# Comu_485.net
KiCad netlist of a schematic drawn in Altium Designer
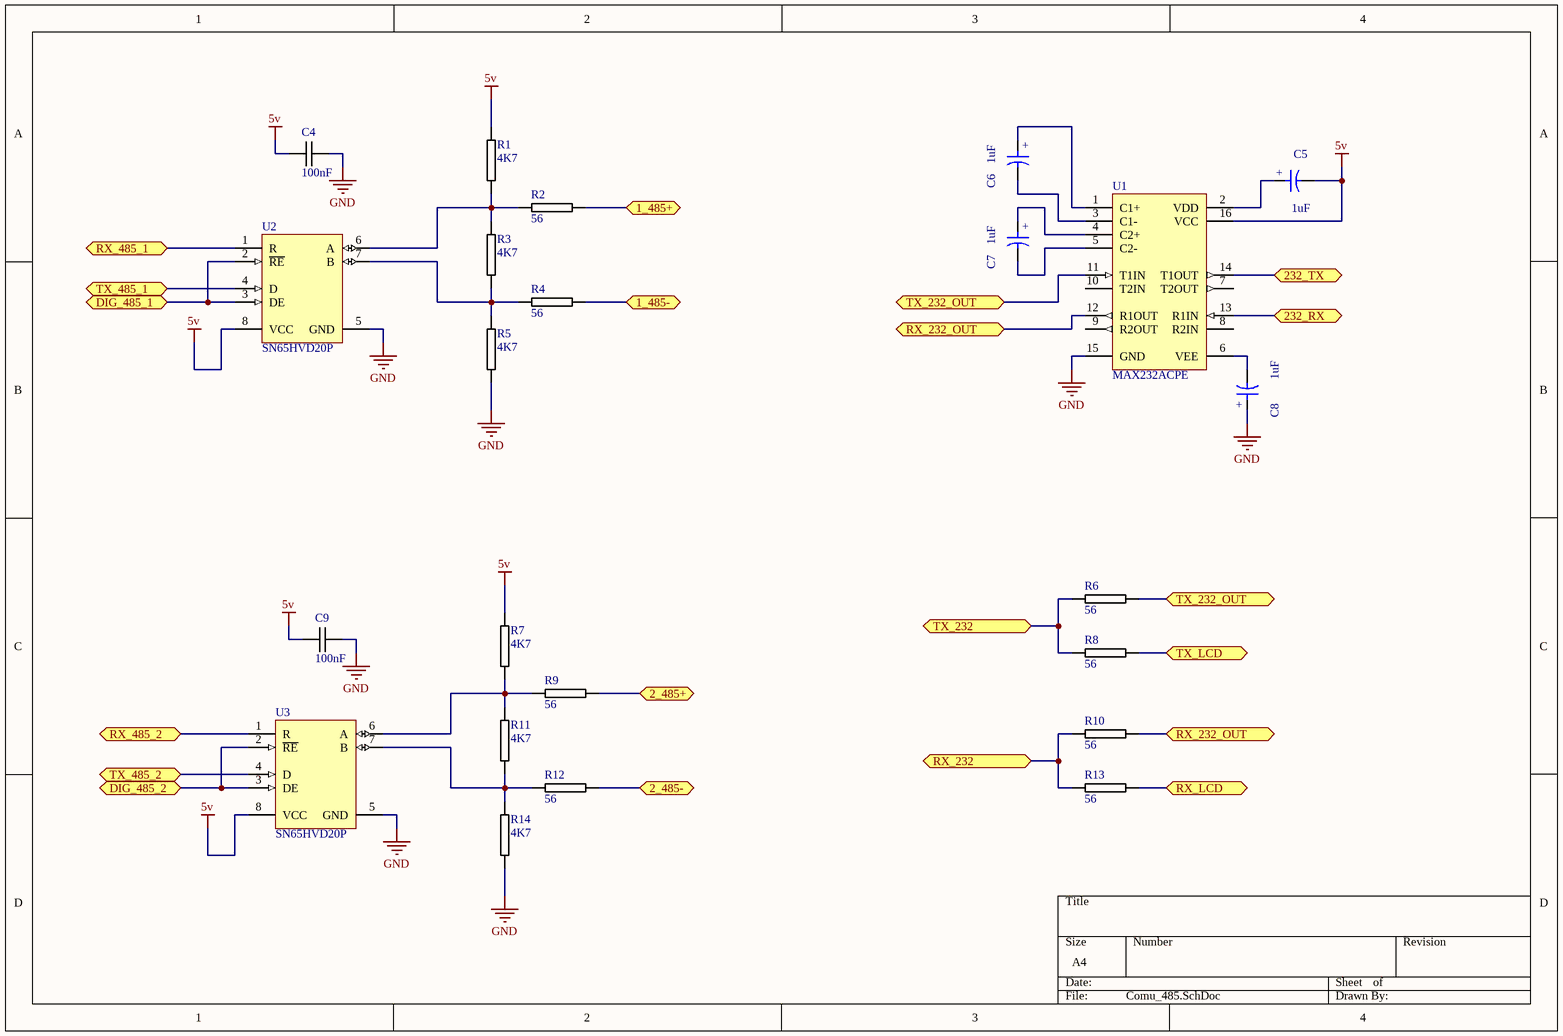
[diagram p0: Comu_485.SchDoc]

(export (version "E")
  (design (tool "Eeschema 10.0.6"))
  (components
    (comp (ref "C4")
      (value "100nF")
      (footprint "0805C-TBD")
      (description "CAPACITOR 0805 CERAMIC")
      (libsource (lib "vh_altium_library") (part "0805C-100nF-25V-X7R-MUR"))
    )
    (comp (ref "C5")
      (value "1uF")
      (footprint "CAPPRB254-450X710")
      (description "Polarised capacitor")
      (fields
        (field (name "PART NUMBER") "CTEB_1UF_35V_10%_254-450X710")
        (field (name "VOLTAGE") "35V")
        (field (name "AUTHOR") "CERN DEM JLC")
      )
      (libsource (lib "Capacitors") (part "Capacitor - polarized"))
    )
    (comp (ref "C6")
      (value "1uF")
      (footprint "CAPPRB254-450X710")
      (description "Polarised capacitor")
      (fields
        (field (name "PART NUMBER") "CTEB_1UF_35V_10%_254-450X710")
        (field (name "VOLTAGE") "35V")
        (field (name "AUTHOR") "CERN DEM JLC")
      )
      (libsource (lib "Capacitors") (part "Capacitor - polarized"))
    )
    (comp (ref "C7")
      (value "1uF")
      (footprint "CAPPRB254-450X710")
      (description "Polarised capacitor")
      (fields
        (field (name "PART NUMBER") "CTEB_1UF_35V_10%_254-450X710")
        (field (name "VOLTAGE") "35V")
        (field (name "AUTHOR") "CERN DEM JLC")
      )
      (libsource (lib "Capacitors") (part "Capacitor - polarized"))
    )
    (comp (ref "C8")
      (value "1uF")
      (footprint "CAPPRB254-450X710")
      (description "Polarised capacitor")
      (fields
        (field (name "PART NUMBER") "CTEB_1UF_35V_10%_254-450X710")
        (field (name "VOLTAGE") "35V")
        (field (name "AUTHOR") "CERN DEM JLC")
      )
      (libsource (lib "Capacitors") (part "Capacitor - polarized"))
    )
    (comp (ref "C9")
      (value "100nF")
      (footprint "0805C-TBD")
      (description "CAPACITOR 0805 CERAMIC")
      (libsource (lib "vh_altium_library") (part "0805C-100nF-25V-X7R-MUR"))
    )
    (comp (ref "R1")
      (value "4K7")
      (footprint "0805R-4K7")
      (description "RESISTOR 0805 1/4 WATT THIN FILM")
      (libsource (lib "vh_altium_library") (part "0805R-4K7"))
    )
    (comp (ref "R2")
      (value "56")
      (footprint "0805R-56")
      (description "RESISTOR 0805 1/4 WATT THIN FILM")
      (libsource (lib "vh_altium_library") (part "0805R-56"))
    )
    (comp (ref "R3")
      (value "4K7")
      (footprint "0805R-4K7")
      (description "RESISTOR 0805 1/4 WATT THIN FILM")
      (libsource (lib "vh_altium_library") (part "0805R-4K7"))
    )
    (comp (ref "R4")
      (value "56")
      (footprint "0805R-56")
      (description "RESISTOR 0805 1/4 WATT THIN FILM")
      (libsource (lib "vh_altium_library") (part "0805R-56"))
    )
    (comp (ref "R5")
      (value "4K7")
      (footprint "0805R-4K7")
      (description "RESISTOR 0805 1/4 WATT THIN FILM")
      (libsource (lib "vh_altium_library") (part "0805R-4K7"))
    )
    (comp (ref "R6")
      (value "56")
      (footprint "0805R-56")
      (description "RESISTOR 0805 1/4 WATT THIN FILM")
      (libsource (lib "vh_altium_library") (part "0805R-56"))
    )
    (comp (ref "R7")
      (value "4K7")
      (footprint "0805R-4K7")
      (description "RESISTOR 0805 1/4 WATT THIN FILM")
      (libsource (lib "vh_altium_library") (part "0805R-4K7"))
    )
    (comp (ref "R8")
      (value "56")
      (footprint "0805R-56")
      (description "RESISTOR 0805 1/4 WATT THIN FILM")
      (libsource (lib "vh_altium_library") (part "0805R-56"))
    )
    (comp (ref "R9")
      (value "56")
      (footprint "0805R-56")
      (description "RESISTOR 0805 1/4 WATT THIN FILM")
      (libsource (lib "vh_altium_library") (part "0805R-56"))
    )
    (comp (ref "R10")
      (value "56")
      (footprint "0805R-56")
      (description "RESISTOR 0805 1/4 WATT THIN FILM")
      (libsource (lib "vh_altium_library") (part "0805R-56"))
    )
    (comp (ref "R11")
      (value "4K7")
      (footprint "0805R-4K7")
      (description "RESISTOR 0805 1/4 WATT THIN FILM")
      (libsource (lib "vh_altium_library") (part "0805R-4K7"))
    )
    (comp (ref "R12")
      (value "56")
      (footprint "0805R-56")
      (description "RESISTOR 0805 1/4 WATT THIN FILM")
      (libsource (lib "vh_altium_library") (part "0805R-56"))
    )
    (comp (ref "R13")
      (value "56")
      (footprint "0805R-56")
      (description "RESISTOR 0805 1/4 WATT THIN FILM")
      (libsource (lib "vh_altium_library") (part "0805R-56"))
    )
    (comp (ref "R14")
      (value "4K7")
      (footprint "0805R-4K7")
      (description "RESISTOR 0805 1/4 WATT THIN FILM")
      (libsource (lib "vh_altium_library") (part "0805R-4K7"))
    )
    (comp (ref "U1")
      (value "MAX232ACPE")
      (footprint "PE16A")
      (description "+5V Powered, Multi-Channel RS-232 Driver/Receiver")
      (fields (field (name "PUBLISHER") "Altium Limited"))
      (libsource (lib "Maxim Communication Transceiver") (part "MAX232ACPE"))
    )
    (comp (ref "U2")
      (value "SN65HVD20P")
      (footprint "P8")
      (fields (field (name "MANUFACTURER") "Texas Instruments"))
      (libsource (lib "Texas Instruments Interface RS-485") (part "SN65HVD20P"))
    )
    (comp (ref "U3")
      (value "SN65HVD20P")
      (footprint "P8")
      (fields (field (name "MANUFACTURER") "Texas Instruments"))
      (libsource (lib "Texas Instruments Interface RS-485") (part "SN65HVD20P"))
    )
  )
  (nets
    (net (code "1") (name "/1_485+") (class "Default") (node (ref "R2") (pin "2") (pintype "passive")))
    (net (code "2") (name "/1_485-") (class "Default") (node (ref "R4") (pin "2") (pintype "passive")))
    (net (code "3") (name "/2_485+") (class "Default") (node (ref "R9") (pin "2") (pintype "passive")))
    (net (code "4") (name "/2_485-") (class "Default") (node (ref "R12") (pin "2") (pintype "passive")))
    (net (code "5") (name "/232_RX") (class "Default")
      (node (ref "U1") (pin "13") (pinfunction "R1IN_13") (pintype "input"))
    )
    (net (code "6") (name "/232_TX") (class "Default")
      (node (ref "U1") (pin "14") (pinfunction "T1OUT_14") (pintype "output"))
    )
    (net (code "7") (name "/DIG_485_1") (class "Default")
      (node (ref "U2") (pin "2") (pinfunction "~{RE}_2") (pintype "input"))
      (node (ref "U2") (pin "3") (pinfunction "DE_3") (pintype "input"))
    )
    (net (code "8") (name "/DIG_485_2") (class "Default")
      (node (ref "U3") (pin "2") (pinfunction "~{RE}_2") (pintype "input"))
      (node (ref "U3") (pin "3") (pinfunction "DE_3") (pintype "input"))
    )
    (net (code "9") (name "/RX_232") (class "Default")
      (node (ref "R10") (pin "1") (pintype "passive"))
      (node (ref "R13") (pin "1") (pintype "passive"))
    )
    (net (code "10") (name "/RX_232_OUT") (class "Default")
      (node (ref "R10") (pin "2") (pintype "passive"))
      (node (ref "U1") (pin "12") (pinfunction "R1OUT_12") (pintype "output"))
    )
    (net (code "11") (name "/RX_485_1") (class "Default")
      (node (ref "U2") (pin "1") (pinfunction "R_1") (pintype "tri_state"))
    )
    (net (code "12") (name "/RX_485_2") (class "Default")
      (node (ref "U3") (pin "1") (pinfunction "R_1") (pintype "tri_state"))
    )
    (net (code "13") (name "/RX_LCD") (class "Default") (node (ref "R13") (pin "2") (pintype "passive")))
    (net (code "14") (name "/TX_232") (class "Default")
      (node (ref "R6") (pin "1") (pintype "passive"))
      (node (ref "R8") (pin "1") (pintype "passive"))
    )
    (net (code "15") (name "/TX_232_OUT") (class "Default")
      (node (ref "R6") (pin "2") (pintype "passive"))
      (node (ref "U1") (pin "11") (pinfunction "T1IN_11") (pintype "input"))
    )
    (net (code "16") (name "/TX_485_1") (class "Default")
      (node (ref "U2") (pin "4") (pinfunction "D_4") (pintype "input"))
    )
    (net (code "17") (name "/TX_485_2") (class "Default")
      (node (ref "U3") (pin "4") (pinfunction "D_4") (pintype "input"))
    )
    (net (code "18") (name "/TX_LCD") (class "Default") (node (ref "R8") (pin "2") (pintype "passive")))
    (net (code "19") (name "5v") (class "Default")
      (node (ref "C4") (pin "1") (pintype "passive"))
      (node (ref "C5") (pin "2") (pinfunction "2_2") (pintype "passive"))
      (node (ref "C9") (pin "1") (pintype "passive"))
      (node (ref "R1") (pin "1") (pintype "passive"))
      (node (ref "R7") (pin "1") (pintype "passive"))
      (node (ref "U1") (pin "16") (pinfunction "VCC_16") (pintype "power_in"))
      (node (ref "U2") (pin "8") (pinfunction "VCC_8") (pintype "power_in"))
      (node (ref "U3") (pin "8") (pinfunction "VCC_8") (pintype "power_in"))
    )
    (net (code "20") (name "GND") (class "Default")
      (node (ref "C4") (pin "2") (pintype "passive"))
      (node (ref "C8") (pin "1") (pinfunction "1_1") (pintype "passive"))
      (node (ref "C9") (pin "2") (pintype "passive"))
      (node (ref "R14") (pin "2") (pintype "passive"))
      (node (ref "R5") (pin "2") (pintype "passive"))
      (node (ref "U1") (pin "15") (pinfunction "GND_15") (pintype "power_in"))
      (node (ref "U2") (pin "5") (pinfunction "GND_5") (pintype "power_in"))
      (node (ref "U3") (pin "5") (pinfunction "GND_5") (pintype "power_in"))
    )
    (net (code "21") (name "Net-(U1-C1+)") (class "Default")
      (node (ref "C6") (pin "1") (pinfunction "1_1") (pintype "passive"))
      (node (ref "U1") (pin "1") (pinfunction "C1+_1") (pintype "passive"))
    )
    (net (code "22") (name "Net-(U1-C1-)") (class "Default")
      (node (ref "C6") (pin "2") (pinfunction "2_2") (pintype "passive"))
      (node (ref "U1") (pin "3") (pinfunction "C1-_3") (pintype "passive"))
    )
    (net (code "23") (name "Net-(U1-C2+)") (class "Default")
      (node (ref "C7") (pin "1") (pinfunction "1_1") (pintype "passive"))
      (node (ref "U1") (pin "4") (pinfunction "C2+_4") (pintype "passive"))
    )
    (net (code "24") (name "Net-(U1-C2-)") (class "Default")
      (node (ref "C7") (pin "2") (pinfunction "2_2") (pintype "passive"))
      (node (ref "U1") (pin "5") (pinfunction "C2-_5") (pintype "passive"))
    )
    (net (code "25") (name "Net-(U1-VDD)") (class "Default")
      (node (ref "C5") (pin "1") (pinfunction "1_1") (pintype "passive"))
      (node (ref "U1") (pin "2") (pinfunction "VDD_2") (pintype "power_in"))
    )
    (net (code "26") (name "Net-(U1-VEE)") (class "Default")
      (node (ref "C8") (pin "2") (pinfunction "2_2") (pintype "passive"))
      (node (ref "U1") (pin "6") (pinfunction "VEE_6") (pintype "power_in"))
    )
    (net (code "27") (name "Net-(U2-A)") (class "Default")
      (node (ref "R1") (pin "2") (pintype "passive"))
      (node (ref "R2") (pin "1") (pintype "passive"))
      (node (ref "R3") (pin "1") (pintype "passive"))
      (node (ref "U2") (pin "6") (pinfunction "A_6") (pintype "bidirectional"))
    )
    (net (code "28") (name "Net-(U2-B)") (class "Default")
      (node (ref "R3") (pin "2") (pintype "passive"))
      (node (ref "R4") (pin "1") (pintype "passive"))
      (node (ref "R5") (pin "1") (pintype "passive"))
      (node (ref "U2") (pin "7") (pinfunction "B_7") (pintype "bidirectional"))
    )
    (net (code "29") (name "Net-(U3-A)") (class "Default")
      (node (ref "R11") (pin "1") (pintype "passive"))
      (node (ref "R7") (pin "2") (pintype "passive"))
      (node (ref "R9") (pin "1") (pintype "passive"))
      (node (ref "U3") (pin "6") (pinfunction "A_6") (pintype "bidirectional"))
    )
    (net (code "30") (name "Net-(U3-B)") (class "Default")
      (node (ref "R11") (pin "2") (pintype "passive"))
      (node (ref "R12") (pin "1") (pintype "passive"))
      (node (ref "R14") (pin "1") (pintype "passive"))
      (node (ref "U3") (pin "7") (pinfunction "B_7") (pintype "bidirectional"))
    )
    (net (code "31") (name "unconnected-(U1-R2IN-Pad8)") (class "Default")
      (node (ref "U1") (pin "8") (pinfunction "R2IN_8") (pintype "passive"))
    )
    (net (code "32") (name "unconnected-(U1-R2OUT-Pad9)") (class "Default")
      (node (ref "U1") (pin "9") (pinfunction "R2OUT_9") (pintype "output"))
    )
    (net (code "33") (name "unconnected-(U1-T2IN-Pad10)") (class "Default")
      (node (ref "U1") (pin "10") (pinfunction "T2IN_10") (pintype "passive"))
    )
    (net (code "34") (name "unconnected-(U1-T2OUT-Pad7)") (class "Default")
      (node (ref "U1") (pin "7") (pinfunction "T2OUT_7") (pintype "output"))
    )
  )
)
